# USB.net
KiCad netlist of a schematic drawn in Altium Designer
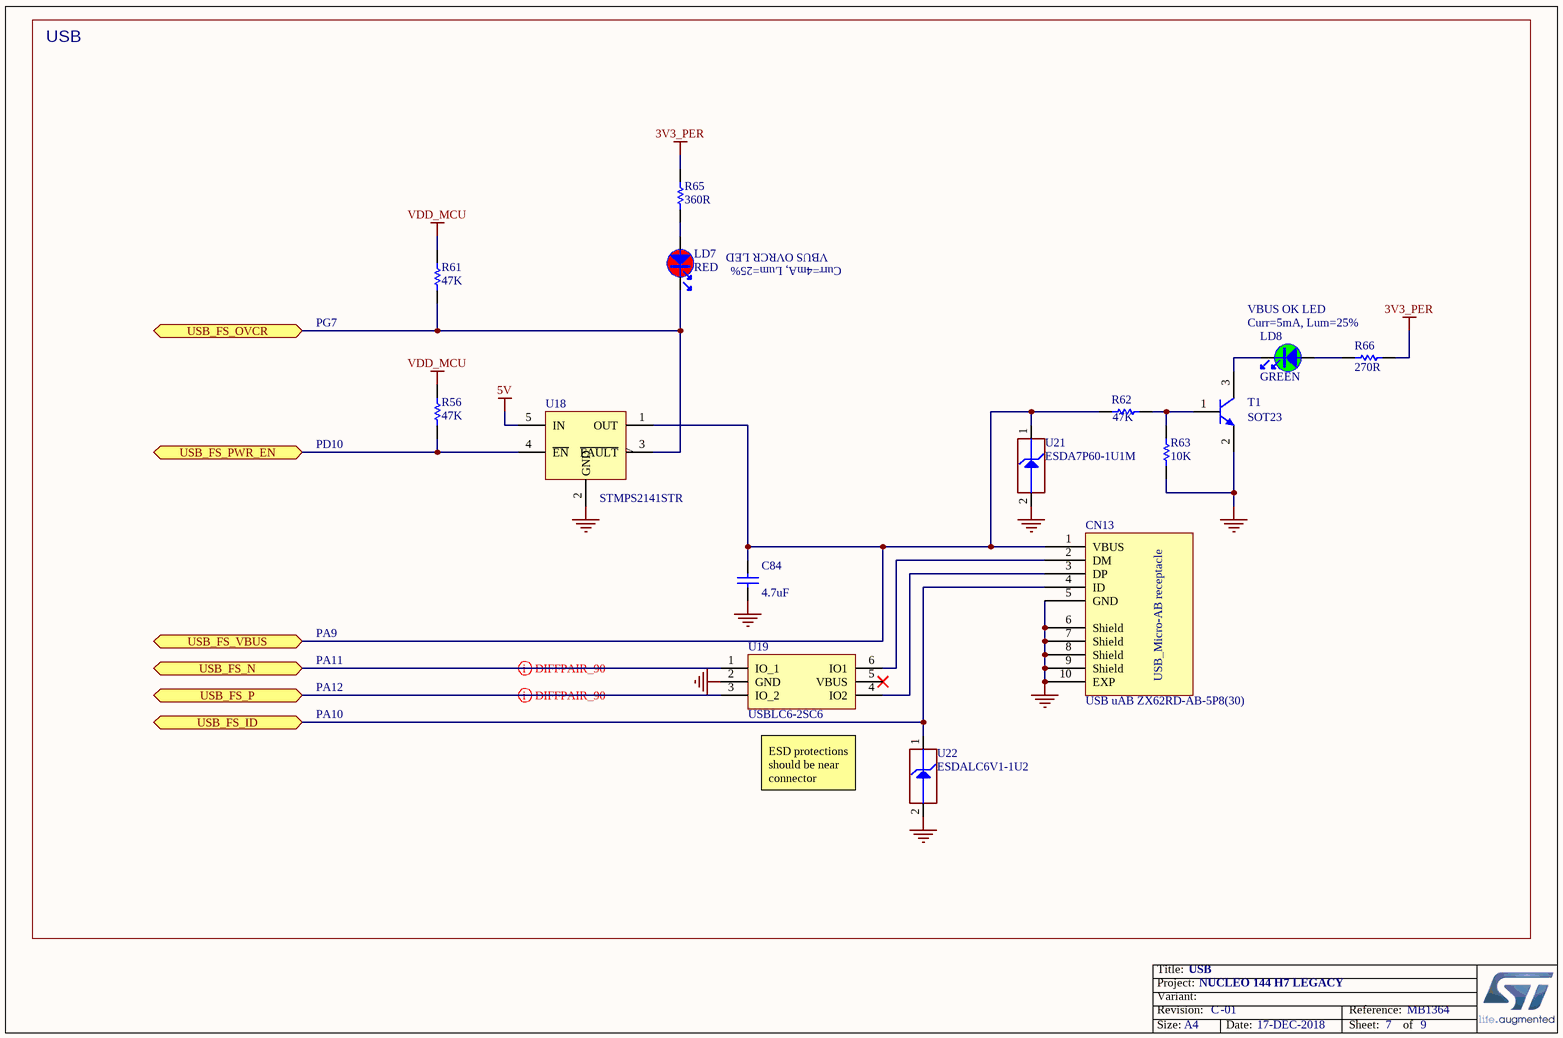
[diagram p0: USB.SchDoc]

(export (version "E")
  (design (tool "Eeschema 10.0.6"))
  (components
    (comp (ref "C84")
      (value "4.7uF")
      (footprint "C0603")
      (description "Capacitor, MLCC, 4.7uF, 16V, X5R, 10%, 0603, T=0.8mm")
      (fields
        (field (name "INTERNAL_PART_NUMBER") "MCD-00009")
        (field (name "MANUFACTURER_PART_NUMBER") "CC0603KRX5R7BB475")
        (field (name "PROVIDED_BY") "SUBCO")
      )
      (libsource (lib "MCD_PARTS_database") (part "Capacitor"))
    )
    (comp (ref "CN13")
      (value "USB uAB ZX62RD-AB-5P8(30)")
      (footprint "CON_USBMICROAB_MOLEX_47590-0001_H3")
      (fields
        (field (name "INTERNAL_PART_NUMBER") "MCD-00661")
        (field (name "MANUFACTURER_PART_NUMBER") "ZX62RD-AB-5P8(30)")
        (field (name "MANUFACTURER") "HIROSE")
        (field (name "PROVIDED_BY") "SUBCO")
      )
      (libsource (lib "MCD_PARTS_database") (part "USB_uAB_47590.0001"))
    )
    (comp (ref "LD7")
      (value "RED")
      (footprint "LED_0603_VISHAY_VLMS1300-GS08_RED_1A2K_H0P8")
      (description "LED Red, 0603 SMD, 2V Forward Voltage")
      (fields
        (field (name "INTERNAL_PART_NUMBER") "MCD-00587")
        (field (name "MANUFACTURER_PART_NUMBER") "VLMS1300-GS08")
        (field (name "PROVIDED_BY") "SUBCO")
      )
      (libsource (lib "MCD_PARTS_database") (part "LED_red"))
    )
    (comp (ref "LD8")
      (value "GREEN")
      (footprint "LED_0603_OSRAM_LG-Q396-PS-35_GREEN_1A2K_H0P4")
      (description "LED Green, 0603 SMD, Forward Voltage Typ=2V, Max=2.5V")
      (fields
        (field (name "INTERNAL_PART_NUMBER") "MCD-00588")
        (field (name "MANUFACTURER_PART_NUMBER") "LG Q396-PS-35")
        (field (name "PROVIDED_BY") "SUBCO")
      )
      (libsource (lib "MCD_PARTS_database") (part "LED_green"))
    )
    (comp (ref "R56")
      (value "47K")
      (footprint "R0402")
      (description "Resistor,47K,0402,1%,1/16W")
      (fields
        (field (name "INTERNAL_PART_NUMBER") "MCD-00063")
        (field (name "MANUFACTURER_PART_NUMBER") "RC0402FR-0747KL")
        (field (name "PROVIDED_BY") "SUBCO")
      )
      (libsource (lib "MCD_PARTS_database") (part "Resistor"))
    )
    (comp (ref "R61")
      (value "47K")
      (footprint "R0402")
      (description "Resistor,47K,0402,1%,1/16W")
      (fields
        (field (name "INTERNAL_PART_NUMBER") "MCD-00063")
        (field (name "MANUFACTURER_PART_NUMBER") "RC0402FR-0747KL")
        (field (name "PROVIDED_BY") "SUBCO")
      )
      (libsource (lib "MCD_PARTS_database") (part "Resistor"))
    )
    (comp (ref "R62")
      (value "47K")
      (footprint "R0402")
      (description "Resistor,47K,0402,1%,1/16W")
      (fields
        (field (name "INTERNAL_PART_NUMBER") "MCD-00063")
        (field (name "MANUFACTURER_PART_NUMBER") "RC0402FR-0747KL")
        (field (name "PROVIDED_BY") "SUBCO")
      )
      (libsource (lib "MCD_PARTS_database") (part "Resistor"))
    )
    (comp (ref "R63")
      (value "10K")
      (footprint "R0402")
      (description "Resistor,10K,0402,1%,1/16W")
      (fields
        (field (name "INTERNAL_PART_NUMBER") "MCD-00053")
        (field (name "MANUFACTURER_PART_NUMBER") "RC0402FR-0710KL")
        (field (name "PROVIDED_BY") "SUBCO")
      )
      (libsource (lib "MCD_PARTS_database") (part "Resistor"))
    )
    (comp (ref "R65")
      (value "360R")
      (footprint "R0402")
      (description "Resistor,360R,0402,1%,1/16W")
      (fields
        (field (name "INTERNAL_PART_NUMBER") "MCD-00461")
        (field (name "MANUFACTURER_PART_NUMBER") "RC0402FR-07360RL")
        (field (name "PROVIDED_BY") "SUBCO")
      )
      (libsource (lib "MCD_PARTS_database") (part "Resistor"))
    )
    (comp (ref "R66")
      (value "270R")
      (footprint "R0402")
      (description "Resistor,270R,0402,1%,1/16W")
      (fields
        (field (name "INTERNAL_PART_NUMBER") "MCD-00441")
        (field (name "MANUFACTURER_PART_NUMBER") "RC0402FR-07270RL")
        (field (name "PROVIDED_BY") "SUBCO")
      )
      (libsource (lib "MCD_PARTS_database") (part "Resistor"))
    )
    (comp (ref "T1")
      (value "SOT23")
      (footprint "NPN_SOT23")
      (description "NPN Bipolar Transistor")
      (fields
        (field (name "INTERNAL_PART_NUMBER") "MCD-00073")
        (field (name "MANUFACTURER_PART_NUMBER") "BSR14")
        (field (name "PROVIDED_BY") "SUBCO")
      )
      (libsource (lib "MCD_PARTS_database") (part "9013-SOT23"))
    )
    (comp (ref "U18")
      (value "STMPS2141STR")
      (footprint "MOS_SOT23-5L")
      (description "Enhanced single channel power switches with active low enable pin")
      (fields
        (field (name "INTERNAL_PART_NUMBER") "MCD-00083")
        (field (name "MANUFACTURER") "STMICROELECTRONICS")
        (field (name "PROVIDED_BY") "SUBCO with ST control")
      )
      (libsource (lib "MCD_PARTS_database") (part "STMPS2141STR"))
    )
    (comp (ref "U19")
      (value "USBLC6-2SC6")
      (footprint "ESD_SOT23-6L")
      (description "Very low capacitance ESD protection")
      (fields
        (field (name "INTERNAL_PART_NUMBER") "MCD-00163")
        (field (name "MANUFACTURER") "STMICROELECTRONICS")
        (field (name "PROVIDED_BY") "SUBCO with ST control")
      )
      (libsource (lib "MCD_PARTS_database") (part "USBLC6-2SC6"))
    )
    (comp (ref "U21")
      (value "ESDA7P60-1U1M")
      (footprint "ESD_QFN2_1P6X1_P125")
      (description "High power transient voltage suppressor, 7V breakdown")
      (fields
        (field (name "INTERNAL_PART_NUMBER") "MCD-00251")
        (field (name "MANUFACTURER") "STMICROELECTRONICS")
        (field (name "PROVIDED_BY") "SUBCO with ST control")
      )
      (libsource (lib "MCD_PARTS_database") (part "ESD-TRANSIL"))
    )
    (comp (ref "U22")
      (value "ESDALC6V1-1U2")
      (footprint "ESD_ST0201")
      (description "ESD protection 6V1")
      (fields
        (field (name "INTERNAL_PART_NUMBER") "MCD-00170")
        (field (name "MANUFACTURER") "STMICROELECTRONICS")
        (field (name "PROVIDED_BY") "SUBCO with ST control")
      )
      (libsource (lib "MCD_PARTS_database") (part "ESD-TRANSIL"))
    )
  )
  (nets
    (net (code "1") (name "/USB_FS_ID") (class "Default")
      (node (ref "CN13") (pin "4") (pinfunction "ID_4") (pintype "passive"))
      (node (ref "U22") (pin "1") (pinfunction "IO1_1") (pintype "passive"))
    )
    (net (code "2") (name "/USB_FS_N") (class "Default")
      (node (ref "U19") (pin "1") (pinfunction "IO_1_1") (pintype "passive"))
    )
    (net (code "3") (name "/USB_FS_OVCR") (class "Default")
      (node (ref "LD7") (pin "2") (pintype "passive"))
      (node (ref "R61") (pin "2") (pinfunction "2_2") (pintype "passive"))
      (node (ref "U18") (pin "3") (pinfunction "~{FAULT}_3") (pintype "passive"))
    )
    (net (code "4") (name "/USB_FS_P") (class "Default")
      (node (ref "U19") (pin "3") (pinfunction "IO_2_3") (pintype "passive"))
    )
    (net (code "5") (name "/USB_FS_PWR_EN") (class "Default")
      (node (ref "R56") (pin "2") (pinfunction "2_2") (pintype "passive"))
      (node (ref "U18") (pin "4") (pinfunction "~{EN}_4") (pintype "passive"))
    )
    (net (code "6") (name "/USB_FS_VBUS") (class "Default")
      (node (ref "C84") (pin "2") (pinfunction "2_2") (pintype "passive"))
      (node (ref "CN13") (pin "1") (pinfunction "VBUS_1") (pintype "passive"))
      (node (ref "R62") (pin "1") (pinfunction "1_1") (pintype "passive"))
      (node (ref "U18") (pin "1") (pinfunction "OUT_1") (pintype "passive"))
      (node (ref "U21") (pin "1") (pinfunction "IO1_1") (pintype "passive"))
    )
    (net (code "7") (name "3V3_PER") (class "Default")
      (node (ref "R65") (pin "2") (pinfunction "2_2") (pintype "passive"))
      (node (ref "R66") (pin "2") (pinfunction "2_2") (pintype "passive"))
    )
    (net (code "8") (name "5V") (class "Default")
      (node (ref "U18") (pin "5") (pinfunction "IN_5") (pintype "passive"))
    )
    (net (code "9") (name "GND") (class "Default")
      (node (ref "C84") (pin "1") (pinfunction "1_1") (pintype "passive"))
      (node (ref "CN13") (pin "10") (pinfunction "EXP_10") (pintype "passive"))
      (node (ref "CN13") (pin "5") (pinfunction "GND_5") (pintype "passive"))
      (node (ref "CN13") (pin "6") (pinfunction "Shield_6") (pintype "passive"))
      (node (ref "CN13") (pin "7") (pinfunction "Shield_7") (pintype "passive"))
      (node (ref "CN13") (pin "8") (pinfunction "Shield_8") (pintype "passive"))
      (node (ref "CN13") (pin "9") (pinfunction "Shield_9") (pintype "passive"))
      (node (ref "R63") (pin "1") (pinfunction "1_1") (pintype "passive"))
      (node (ref "T1") (pin "2") (pinfunction "E_2") (pintype "passive"))
      (node (ref "U18") (pin "2") (pinfunction "GND_2") (pintype "passive"))
      (node (ref "U19") (pin "2") (pinfunction "GND_2") (pintype "passive"))
      (node (ref "U21") (pin "2") (pinfunction "GND_2") (pintype "passive"))
      (node (ref "U22") (pin "2") (pinfunction "GND_2") (pintype "passive"))
    )
    (net (code "10") (name "Net-(CN13-DM)") (class "Default")
      (node (ref "CN13") (pin "2") (pinfunction "DM_2") (pintype "passive"))
      (node (ref "U19") (pin "6") (pinfunction "IO1_6") (pintype "passive"))
    )
    (net (code "11") (name "Net-(CN13-DP)") (class "Default")
      (node (ref "CN13") (pin "3") (pinfunction "DP_3") (pintype "passive"))
      (node (ref "U19") (pin "4") (pinfunction "IO2_4") (pintype "passive"))
    )
    (net (code "12") (name "Net-(LD7-Pad1)") (class "Default")
      (node (ref "LD7") (pin "1") (pintype "passive"))
      (node (ref "R65") (pin "1") (pinfunction "1_1") (pintype "passive"))
    )
    (net (code "13") (name "Net-(LD8-Pad1)") (class "Default")
      (node (ref "LD8") (pin "1") (pintype "passive"))
      (node (ref "R66") (pin "1") (pinfunction "1_1") (pintype "passive"))
    )
    (net (code "14") (name "Net-(T1-B)") (class "Default")
      (node (ref "R62") (pin "2") (pinfunction "2_2") (pintype "passive"))
      (node (ref "R63") (pin "2") (pinfunction "2_2") (pintype "passive"))
      (node (ref "T1") (pin "1") (pinfunction "B_1") (pintype "passive"))
    )
    (net (code "15") (name "Net-(T1-C)") (class "Default")
      (node (ref "LD8") (pin "2") (pintype "passive"))
      (node (ref "T1") (pin "3") (pinfunction "C_3") (pintype "passive"))
    )
    (net (code "16") (name "VDD_MCU") (class "Default")
      (node (ref "R56") (pin "1") (pinfunction "1_1") (pintype "passive"))
      (node (ref "R61") (pin "1") (pinfunction "1_1") (pintype "passive"))
    )
    (net (code "17") (name "unconnected-(U19-VBUS-Pad5)") (class "Default")
      (node (ref "U19") (pin "5") (pinfunction "VBUS_5") (pintype "passive+no_connect"))
    )
  )
)
